# SLAYER_ESP32_M1U.net
KiCad netlist of a schematic drawn in Altium Designer
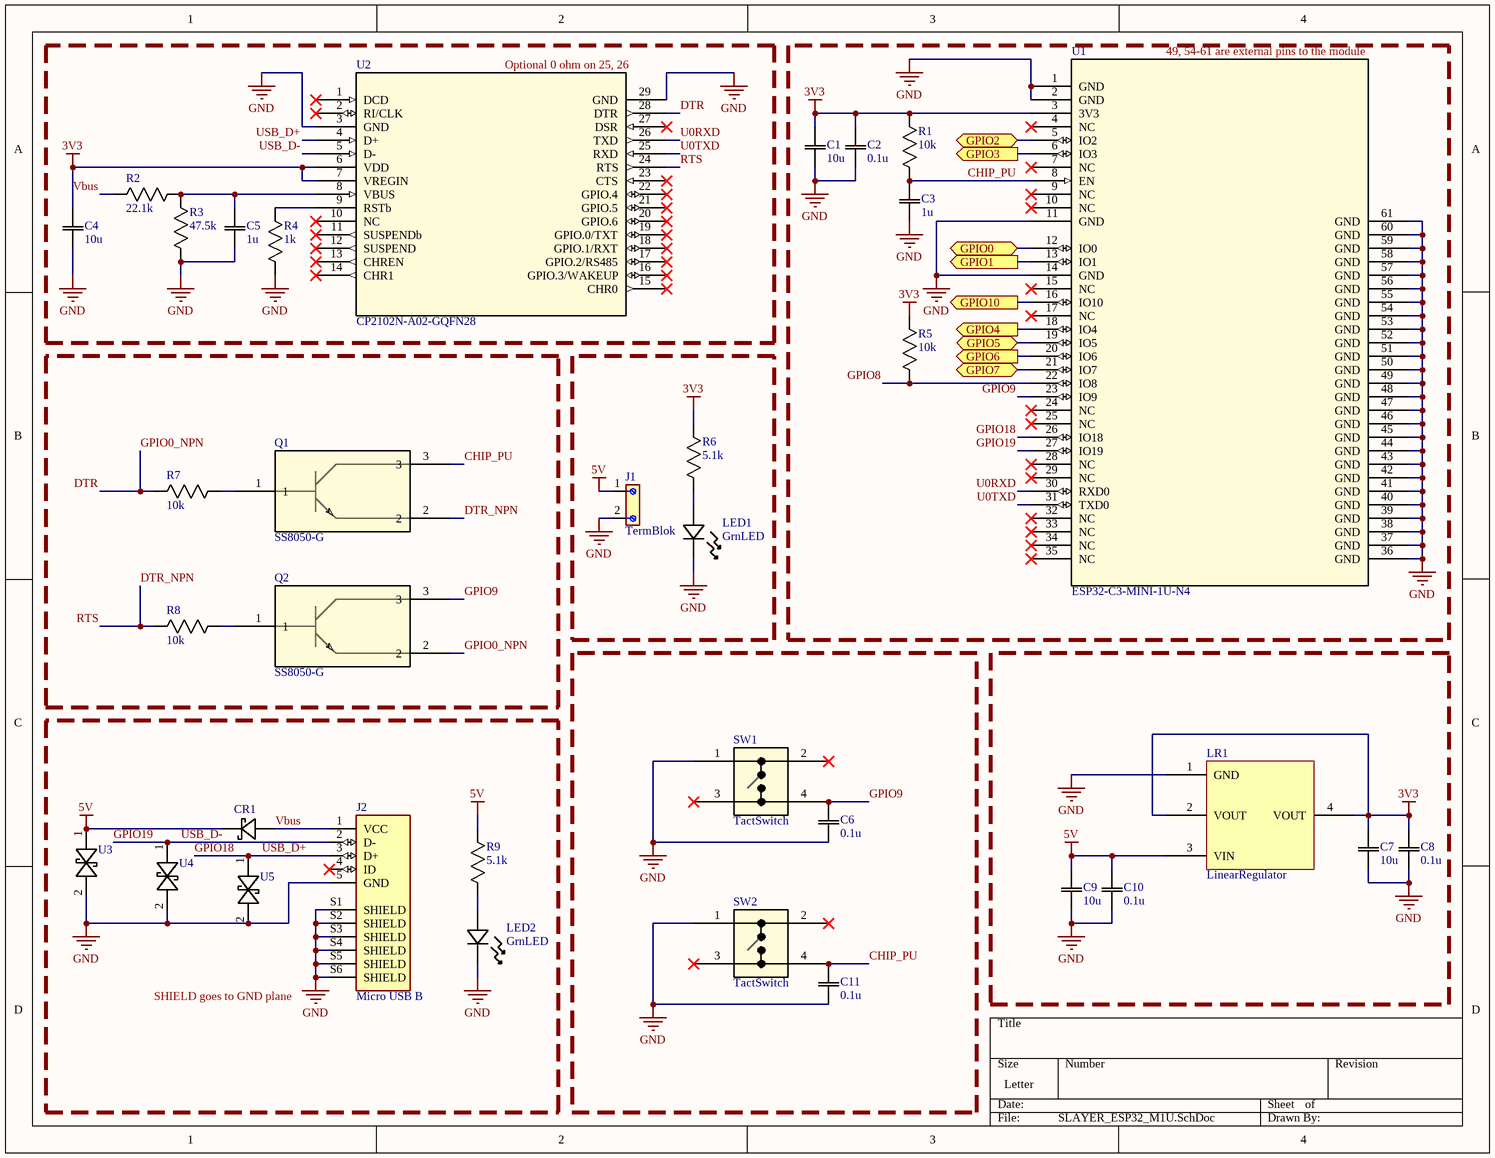
[diagram p0: SLAYER_ESP32_M1U.SchDoc]

(export (version "E")
  (design (tool "Eeschema 10.0.6"))
  (components
    (comp (ref "C1")
      (value "10u")
      (footprint "10uF/25V/0603")
      (description "GRM188R61E106KA73D")
      (fields (field (name "COPYRIGHT") "Copyright (C) 2026 Ultra Librarian. All rights reserved."))
      (libsource (lib "SLAYER_Altium_Sch") (part "10uF/25V"))
    )
    (comp (ref "C2")
      (value "0.1u")
      (footprint "0.1uF/50V")
      (description "CC0603KRX7R9BB104")
      (fields (field (name "COPYRIGHT") "Copyright (C) 2025 Ultra Librarian. All rights reserved."))
      (libsource (lib "SLAYER_Altium_Sch") (part "0.1uF/50V"))
    )
    (comp (ref "C3")
      (value "1u")
      (footprint "1uF/16V")
      (description "CL10B105KO8NNNC")
      (fields (field (name "COPYRIGHT") "Copyright (C) 2025 Ultra Librarian. All rights reserved."))
      (libsource (lib "SLAYER_Altium_Sch") (part "1uF/16V"))
    )
    (comp (ref "C4")
      (value "10u")
      (footprint "10uF/25V/0603")
      (description "GRM188R61E106KA73D")
      (fields (field (name "COPYRIGHT") "Copyright (C) 2026 Ultra Librarian. All rights reserved."))
      (libsource (lib "SLAYER_Altium_Sch") (part "10uF/25V"))
    )
    (comp (ref "C5")
      (value "1u")
      (footprint "1uF/16V")
      (description "CL10B105KO8NNNC")
      (fields (field (name "COPYRIGHT") "Copyright (C) 2025 Ultra Librarian. All rights reserved."))
      (libsource (lib "SLAYER_Altium_Sch") (part "1uF/16V"))
    )
    (comp (ref "C6")
      (value "0.1u")
      (footprint "0.1uF/50V")
      (description "CC0603KRX7R9BB104")
      (fields (field (name "COPYRIGHT") "Copyright (C) 2025 Ultra Librarian. All rights reserved."))
      (libsource (lib "SLAYER_Altium_Sch") (part "0.1uF/50V"))
    )
    (comp (ref "C7")
      (value "10u")
      (footprint "10uF/25V/0603")
      (description "GRM188R61E106KA73D")
      (fields (field (name "COPYRIGHT") "Copyright (C) 2026 Ultra Librarian. All rights reserved."))
      (libsource (lib "SLAYER_Altium_Sch") (part "10uF/25V"))
    )
    (comp (ref "C8")
      (value "0.1u")
      (footprint "0.1uF/50V")
      (description "CC0603KRX7R9BB104")
      (fields (field (name "COPYRIGHT") "Copyright (C) 2025 Ultra Librarian. All rights reserved."))
      (libsource (lib "SLAYER_Altium_Sch") (part "0.1uF/50V"))
    )
    (comp (ref "C9")
      (value "10u")
      (footprint "10uF/25V/0603")
      (description "GRM188R61E106KA73D")
      (fields (field (name "COPYRIGHT") "Copyright (C) 2026 Ultra Librarian. All rights reserved."))
      (libsource (lib "SLAYER_Altium_Sch") (part "10uF/25V"))
    )
    (comp (ref "C10")
      (value "0.1u")
      (footprint "0.1uF/50V")
      (description "CC0603KRX7R9BB104")
      (fields (field (name "COPYRIGHT") "Copyright (C) 2025 Ultra Librarian. All rights reserved."))
      (libsource (lib "SLAYER_Altium_Sch") (part "0.1uF/50V"))
    )
    (comp (ref "C11")
      (value "0.1u")
      (footprint "0.1uF/50V")
      (description "CC0603KRX7R9BB104")
      (fields (field (name "COPYRIGHT") "Copyright (C) 2025 Ultra Librarian. All rights reserved."))
      (libsource (lib "SLAYER_Altium_Sch") (part "0.1uF/50V"))
    )
    (comp (ref "CR1")
      (value "B5819W-TP")
      (footprint "Schottky Diode")
      (fields (field (name "COPYRIGHT") "Copyright (C) 2025 Ultra Librarian. All rights reserved."))
      (libsource (lib "SLAYER_Altium_Sch") (part "Schottky Diode"))
    )
    (comp (ref "J1")
      (value "TermBlok")
      (footprint "TerminalBlock")
      (description "691137710002")
      (fields (field (name "MF") "WÃ¼rth Elektronik"))
      (libsource (lib "SLAYER_Altium_Sch") (part "2TerminalBlock"))
    )
    (comp (ref "J2")
      (value "Micro USB B")
      (footprint "Micro_USB_B")
      (description "10118192-0002LF")
      (fields (field (name "MF") "Amphenol ICC"))
      (libsource (lib "SLAYER_Altium_Sch") (part "Micro USB B"))
    )
    (comp (ref "LED1")
      (value "GrnLED")
      (footprint "GreenLED")
      (description "LTST-C190KGKT")
      (fields (field (name "COPYRIGHT") "Copyright (C) 2025 Ultra Librarian. All rights reserved."))
      (libsource (lib "SLAYER_Altium_Sch") (part "GreenLED"))
    )
    (comp (ref "LED2")
      (value "GrnLED")
      (footprint "GreenLED")
      (description "LTST-C190KGKT")
      (fields (field (name "COPYRIGHT") "Copyright (C) 2025 Ultra Librarian. All rights reserved."))
      (libsource (lib "SLAYER_Altium_Sch") (part "GreenLED"))
    )
    (comp (ref "LR1")
      (value "LinearRegulator")
      (footprint "LinearRegulator")
      (description "SGM2212-3.3XKC3G/TR")
      (libsource (lib "SLAYER_Altium_Sch") (part "LinearRegulator"))
    )
    (comp (ref "Q1")
      (value "SS8050-G")
      (footprint "NPN/25V/1.5A")
      (fields (field (name "COPYRIGHT") "Copyright (C) 2026 Ultra Librarian. All rights reserved."))
      (libsource (lib "SLAYER_Altium_Sch") (part "NPN/25V/1.5A"))
    )
    (comp (ref "Q2")
      (value "SS8050-G")
      (footprint "NPN/25V/1.5A")
      (fields (field (name "COPYRIGHT") "Copyright (C) 2026 Ultra Librarian. All rights reserved."))
      (libsource (lib "SLAYER_Altium_Sch") (part "NPN/25V/1.5A"))
    )
    (comp (ref "R1")
      (value "10k")
      (footprint "10k/0.125W")
      (description "CRCW060310K0FKEA")
      (fields (field (name "COPYRIGHT") "Copyright (C) 2025 Ultra Librarian. All rights reserved."))
      (libsource (lib "SLAYER_Altium_Sch") (part "10k/0.125W"))
    )
    (comp (ref "R2")
      (value "22.1k")
      (footprint "22.1k/0.125W")
      (description "CRCW060322K1FKEA")
      (fields (field (name "COPYRIGHT") "Copyright (C) 2025 Ultra Librarian. All rights reserved."))
      (libsource (lib "SLAYER_Altium_Sch") (part "22.1k/0.125W"))
    )
    (comp (ref "R3")
      (value "47.5k")
      (footprint "47.5k/0.125W")
      (description "CRCW060347K5FKEA")
      (fields (field (name "COPYRIGHT") "Copyright (C) 2026 Ultra Librarian. All rights reserved."))
      (libsource (lib "SLAYER_Altium_Sch") (part "47.5k/0.125W"))
    )
    (comp (ref "R4")
      (value "1k")
      (footprint "1k/0.125W")
      (description "CRCW06031K00FKEA")
      (fields (field (name "COPYRIGHT") "Copyright (C) 2026 Ultra Librarian. All rights reserved."))
      (libsource (lib "SLAYER_Altium_Sch") (part "1k/0.125W"))
    )
    (comp (ref "R5")
      (value "10k")
      (footprint "10k/0.125W")
      (description "CRCW060310K0FKEA")
      (fields (field (name "COPYRIGHT") "Copyright (C) 2025 Ultra Librarian. All rights reserved."))
      (libsource (lib "SLAYER_Altium_Sch") (part "10k/0.125W"))
    )
    (comp (ref "R6")
      (value "5.1k")
      (footprint "5.1k/0.25W")
      (description "CRCW08055K10FKEA")
      (fields (field (name "COPYRIGHT") "Copyright (C) 2026 Ultra Librarian. All rights reserved."))
      (libsource (lib "SLAYER_Altium_Sch") (part "5.1k/0.25W"))
    )
    (comp (ref "R7")
      (value "10k")
      (footprint "10k/0.125W")
      (description "CRCW060310K0FKEA")
      (fields (field (name "COPYRIGHT") "Copyright (C) 2025 Ultra Librarian. All rights reserved."))
      (libsource (lib "SLAYER_Altium_Sch") (part "10k/0.125W"))
    )
    (comp (ref "R8")
      (value "10k")
      (footprint "10k/0.125W")
      (description "CRCW060310K0FKEA")
      (fields (field (name "COPYRIGHT") "Copyright (C) 2025 Ultra Librarian. All rights reserved."))
      (libsource (lib "SLAYER_Altium_Sch") (part "10k/0.125W"))
    )
    (comp (ref "R9")
      (value "5.1k")
      (footprint "5.1k/0.25W")
      (description "CRCW08055K10FKEA")
      (fields (field (name "COPYRIGHT") "Copyright (C) 2026 Ultra Librarian. All rights reserved."))
      (libsource (lib "SLAYER_Altium_Sch") (part "5.1k/0.25W"))
    )
    (comp (ref "SW1")
      (value "TactSwitch")
      (footprint "TactSwitch")
      (description "PTS815 SJM 250 SMTR LFS")
      (fields (field (name "COPYRIGHT") "Copyright (C) 2026 Ultra Librarian. All rights reserved."))
      (libsource (lib "SLAYER_Altium_Sch") (part "TactSwitch"))
    )
    (comp (ref "SW2")
      (value "TactSwitch")
      (footprint "TactSwitch")
      (description "PTS815 SJM 250 SMTR LFS")
      (fields (field (name "COPYRIGHT") "Copyright (C) 2026 Ultra Librarian. All rights reserved."))
      (libsource (lib "SLAYER_Altium_Sch") (part "TactSwitch"))
    )
    (comp (ref "U1")
      (value "ESP32-C3-MINI-1U-N4")
      (footprint "ESP32-C3-MINI-1U_EXP")
      (description "Description")
      (fields (field (name "COPYRIGHT") "Copyright (C) 2025 Ultra Librarian. All rights reserved."))
      (libsource (lib "SLAYER_Altium_Sch") (part "ESP32-C3-MINI-1U-N4"))
    )
    (comp (ref "U2")
      (value "CP2102N-A02-GQFN28")
      (footprint "USB to UART")
      (fields (field (name "COPYRIGHT") "Copyright (C) 2025 Ultra Librarian. All rights reserved."))
      (libsource (lib "SLAYER_Altium_Sch") (part "USB to UART"))
    )
    (comp (ref "U3")
      (value "ESD5B5.0ST1G")
      (footprint "TVS Diode")
      (fields (field (name "COPYRIGHT") "Copyright (C) 2025 Ultra Librarian. All rights reserved."))
      (libsource (lib "SLAYER_Altium_Sch") (part "TVS Diode"))
    )
    (comp (ref "U4")
      (value "ESD5B5.0ST1G")
      (footprint "TVS Diode")
      (fields (field (name "COPYRIGHT") "Copyright (C) 2025 Ultra Librarian. All rights reserved."))
      (libsource (lib "SLAYER_Altium_Sch") (part "TVS Diode"))
    )
    (comp (ref "U5")
      (value "ESD5B5.0ST1G")
      (footprint "TVS Diode")
      (fields (field (name "COPYRIGHT") "Copyright (C) 2025 Ultra Librarian. All rights reserved."))
      (libsource (lib "SLAYER_Altium_Sch") (part "TVS Diode"))
    )
  )
  (nets
    (net (code "1") (name "/CHIP_PU") (class "Default")
      (node (ref "C11") (pin "2") (pinfunction "2_2") (pintype "passive"))
      (node (ref "C3") (pin "2") (pinfunction "2_2") (pintype "passive"))
      (node (ref "Q1") (pin "3") (pinfunction "3_3") (pintype "passive"))
      (node (ref "R1") (pin "2") (pinfunction "2_2") (pintype "passive"))
      (node (ref "SW2") (pin "4") (pinfunction "4_4") (pintype "passive"))
      (node (ref "U1") (pin "8") (pinfunction "EN_8") (pintype "input"))
    )
    (net (code "2") (name "/DTR") (class "Default")
      (node (ref "Q2") (pin "2") (pinfunction "2_2") (pintype "passive"))
      (node (ref "R7") (pin "2") (pinfunction "2_2") (pintype "passive"))
      (node (ref "U2") (pin "28") (pinfunction "DTR_28") (pintype "output"))
    )
    (net (code "3") (name "/DTR_NPN") (class "Default")
      (node (ref "Q1") (pin "2") (pinfunction "2_2") (pintype "passive"))
      (node (ref "R8") (pin "2") (pinfunction "2_2") (pintype "passive"))
      (node (ref "U2") (pin "24") (pinfunction "RTS_24") (pintype "output"))
    )
    (net (code "4") (name "/GPIO0") (class "Default")
      (node (ref "U1") (pin "12") (pinfunction "IO0_12") (pintype "bidirectional"))
    )
    (net (code "5") (name "/GPIO1") (class "Default")
      (node (ref "U1") (pin "13") (pinfunction "IO1_13") (pintype "bidirectional"))
    )
    (net (code "6") (name "/GPIO2") (class "Default")
      (node (ref "U1") (pin "5") (pinfunction "IO2_5") (pintype "bidirectional"))
    )
    (net (code "7") (name "/GPIO3") (class "Default")
      (node (ref "U1") (pin "6") (pinfunction "IO3_6") (pintype "bidirectional"))
    )
    (net (code "8") (name "/GPIO4") (class "Default")
      (node (ref "U1") (pin "18") (pinfunction "IO4_18") (pintype "bidirectional"))
    )
    (net (code "9") (name "/GPIO5") (class "Default")
      (node (ref "U1") (pin "19") (pinfunction "IO5_19") (pintype "bidirectional"))
    )
    (net (code "10") (name "/GPIO6") (class "Default")
      (node (ref "U1") (pin "20") (pinfunction "IO6_20") (pintype "bidirectional"))
    )
    (net (code "11") (name "/GPIO7") (class "Default")
      (node (ref "U1") (pin "21") (pinfunction "IO7_21") (pintype "bidirectional"))
    )
    (net (code "12") (name "/GPIO8") (class "Default")
      (node (ref "R5") (pin "2") (pinfunction "2_2") (pintype "passive"))
      (node (ref "U1") (pin "22") (pinfunction "IO8_22") (pintype "bidirectional"))
    )
    (net (code "13") (name "/GPIO9") (class "Default")
      (node (ref "C6") (pin "2") (pinfunction "2_2") (pintype "passive"))
      (node (ref "Q2") (pin "3") (pinfunction "3_3") (pintype "passive"))
      (node (ref "SW1") (pin "4") (pinfunction "4_4") (pintype "passive"))
      (node (ref "U1") (pin "23") (pinfunction "IO9_23") (pintype "bidirectional"))
    )
    (net (code "14") (name "/GPIO10") (class "Default")
      (node (ref "U1") (pin "16") (pinfunction "IO10_16") (pintype "bidirectional"))
    )
    (net (code "15") (name "/GPIO18") (class "Default")
      (node (ref "J2") (pin "3") (pinfunction "D+_3") (pintype "bidirectional"))
      (node (ref "U1") (pin "26") (pinfunction "IO18_26") (pintype "bidirectional"))
      (node (ref "U2") (pin "4") (pinfunction "D+_4") (pintype "input"))
      (node (ref "U5") (pin "1") (pinfunction "1_1") (pintype "passive"))
    )
    (net (code "16") (name "/GPIO19") (class "Default")
      (node (ref "J2") (pin "2") (pinfunction "D-_2") (pintype "bidirectional"))
      (node (ref "U1") (pin "27") (pinfunction "IO19_27") (pintype "bidirectional"))
      (node (ref "U2") (pin "5") (pinfunction "D-_5") (pintype "input"))
      (node (ref "U4") (pin "1") (pinfunction "1_1") (pintype "passive"))
    )
    (net (code "17") (name "/U0RXD") (class "Default")
      (node (ref "U1") (pin "30") (pinfunction "RXD0_30") (pintype "bidirectional"))
      (node (ref "U2") (pin "26") (pinfunction "TXD_26") (pintype "output"))
    )
    (net (code "18") (name "/U0TXD") (class "Default")
      (node (ref "U1") (pin "31") (pinfunction "TXD0_31") (pintype "bidirectional"))
      (node (ref "U2") (pin "25") (pinfunction "RXD_25") (pintype "input"))
    )
    (net (code "19") (name "/Vbus") (class "Default")
      (node (ref "CR1") (pin "2") (pinfunction "2_2") (pintype "passive"))
      (node (ref "J2") (pin "1") (pinfunction "VCC_1") (pintype "power_in"))
      (node (ref "R2") (pin "2") (pinfunction "2_2") (pintype "passive"))
    )
    (net (code "20") (name "3V3") (class "Default")
      (node (ref "C1") (pin "2") (pinfunction "2_2") (pintype "passive"))
      (node (ref "C2") (pin "2") (pinfunction "2_2") (pintype "passive"))
      (node (ref "C4") (pin "2") (pinfunction "2_2") (pintype "passive"))
      (node (ref "C7") (pin "2") (pinfunction "2_2") (pintype "passive"))
      (node (ref "C8") (pin "2") (pinfunction "2_2") (pintype "passive"))
      (node (ref "LR1") (pin "2") (pinfunction "VOUT_2") (pintype "power_in"))
      (node (ref "LR1") (pin "4") (pinfunction "VOUT_4") (pintype "power_in"))
      (node (ref "R1") (pin "1") (pinfunction "1_1") (pintype "passive"))
      (node (ref "R5") (pin "1") (pinfunction "1_1") (pintype "passive"))
      (node (ref "R6") (pin "1") (pinfunction "1_1") (pintype "passive"))
      (node (ref "U1") (pin "3") (pinfunction "3V3_3") (pintype "power_in"))
      (node (ref "U2") (pin "6") (pinfunction "VDD_6") (pintype "power_in"))
      (node (ref "U2") (pin "7") (pinfunction "VREGIN_7") (pintype "power_in"))
    )
    (net (code "21") (name "5V") (class "Default")
      (node (ref "C10") (pin "2") (pinfunction "2_2") (pintype "passive"))
      (node (ref "C9") (pin "2") (pinfunction "2_2") (pintype "passive"))
      (node (ref "CR1") (pin "1") (pinfunction "1_1") (pintype "passive"))
      (node (ref "J1") (pin "1") (pinfunction "1_1") (pintype "passive"))
      (node (ref "LR1") (pin "3") (pinfunction "VIN_3") (pintype "power_in"))
      (node (ref "R9") (pin "1") (pinfunction "1_1") (pintype "passive"))
      (node (ref "U3") (pin "1") (pinfunction "1_1") (pintype "passive"))
    )
    (net (code "22") (name "GND") (class "Default")
      (node (ref "C1") (pin "1") (pinfunction "1_1") (pintype "passive"))
      (node (ref "C10") (pin "1") (pinfunction "1_1") (pintype "passive"))
      (node (ref "C11") (pin "1") (pinfunction "1_1") (pintype "passive"))
      (node (ref "C2") (pin "1") (pinfunction "1_1") (pintype "passive"))
      (node (ref "C3") (pin "1") (pinfunction "1_1") (pintype "passive"))
      (node (ref "C4") (pin "1") (pinfunction "1_1") (pintype "passive"))
      (node (ref "C5") (pin "1") (pinfunction "1_1") (pintype "passive"))
      (node (ref "C6") (pin "1") (pinfunction "1_1") (pintype "passive"))
      (node (ref "C7") (pin "1") (pinfunction "1_1") (pintype "passive"))
      (node (ref "C8") (pin "1") (pinfunction "1_1") (pintype "passive"))
      (node (ref "C9") (pin "1") (pinfunction "1_1") (pintype "passive"))
      (node (ref "J1") (pin "2") (pinfunction "2_2") (pintype "passive"))
      (node (ref "J2") (pin "5") (pinfunction "GND_5") (pintype "power_in"))
      (node (ref "J2") (pin "S1") (pinfunction "SHIELD_S1") (pintype "passive"))
      (node (ref "J2") (pin "S2") (pinfunction "SHIELD_S2") (pintype "passive"))
      (node (ref "J2") (pin "S3") (pinfunction "SHIELD_S3") (pintype "passive"))
      (node (ref "J2") (pin "S4") (pinfunction "SHIELD_S4") (pintype "passive"))
      (node (ref "J2") (pin "S5") (pinfunction "SHIELD_S5") (pintype "passive"))
      (node (ref "J2") (pin "S6") (pinfunction "SHIELD_S6") (pintype "passive"))
      (node (ref "LED1") (pin "1") (pinfunction "1_1") (pintype "passive"))
      (node (ref "LED2") (pin "1") (pinfunction "1_1") (pintype "passive"))
      (node (ref "LR1") (pin "1") (pinfunction "GND_1") (pintype "power_in"))
      (node (ref "R3") (pin "2") (pinfunction "2_2") (pintype "passive"))
      (node (ref "R4") (pin "2") (pinfunction "2_2") (pintype "passive"))
      (node (ref "SW1") (pin "1") (pinfunction "1_1") (pintype "passive"))
      (node (ref "SW2") (pin "1") (pinfunction "1_1") (pintype "passive"))
      (node (ref "U1") (pin "1") (pinfunction "GND_1") (pintype "power_in"))
      (node (ref "U1") (pin "11") (pinfunction "GND_11") (pintype "power_in"))
      (node (ref "U1") (pin "14") (pinfunction "GND_14") (pintype "power_in"))
      (node (ref "U1") (pin "2") (pinfunction "GND_2") (pintype "power_in"))
      (node (ref "U1") (pin "36") (pinfunction "GND_36") (pintype "power_in"))
      (node (ref "U1") (pin "37") (pinfunction "GND_37") (pintype "power_in"))
      (node (ref "U1") (pin "38") (pinfunction "GND_38") (pintype "power_in"))
      (node (ref "U1") (pin "39") (pinfunction "GND_39") (pintype "power_in"))
      (node (ref "U1") (pin "40") (pinfunction "GND_40") (pintype "power_in"))
      (node (ref "U1") (pin "41") (pinfunction "GND_41") (pintype "power_in"))
      (node (ref "U1") (pin "42") (pinfunction "GND_42") (pintype "power_in"))
      (node (ref "U1") (pin "43") (pinfunction "GND_43") (pintype "power_in"))
      (node (ref "U1") (pin "44") (pinfunction "GND_44") (pintype "power_in"))
      (node (ref "U1") (pin "45") (pinfunction "GND_45") (pintype "power_in"))
      (node (ref "U1") (pin "46") (pinfunction "GND_46") (pintype "power_in"))
      (node (ref "U1") (pin "47") (pinfunction "GND_47") (pintype "power_in"))
      (node (ref "U1") (pin "48") (pinfunction "GND_48") (pintype "power_in"))
      (node (ref "U1") (pin "49") (pinfunction "GND_49") (pintype "power_in"))
      (node (ref "U1") (pin "50") (pinfunction "GND_50") (pintype "power_in"))
      (node (ref "U1") (pin "51") (pinfunction "GND_51") (pintype "power_in"))
      (node (ref "U1") (pin "52") (pinfunction "GND_52") (pintype "power_in"))
      (node (ref "U1") (pin "53") (pinfunction "GND_53") (pintype "power_in"))
      (node (ref "U1") (pin "54") (pinfunction "GND_54") (pintype "power_in"))
      (node (ref "U1") (pin "55") (pinfunction "GND_55") (pintype "power_in"))
      (node (ref "U1") (pin "56") (pinfunction "GND_56") (pintype "power_in"))
      (node (ref "U1") (pin "57") (pinfunction "GND_57") (pintype "power_in"))
      (node (ref "U1") (pin "58") (pinfunction "GND_58") (pintype "power_in"))
      (node (ref "U1") (pin "59") (pinfunction "GND_59") (pintype "power_in"))
      (node (ref "U1") (pin "60") (pinfunction "GND_60") (pintype "power_in"))
      (node (ref "U1") (pin "61") (pinfunction "GND_61") (pintype "power_in"))
      (node (ref "U2") (pin "29") (pinfunction "GND_29") (pintype "power_in"))
      (node (ref "U2") (pin "3") (pinfunction "GND_3") (pintype "power_in"))
      (node (ref "U3") (pin "2") (pinfunction "2_2") (pintype "passive"))
      (node (ref "U4") (pin "2") (pinfunction "2_2") (pintype "passive"))
      (node (ref "U5") (pin "2") (pinfunction "2_2") (pintype "passive"))
    )
    (net (code "23") (name "Net-(LED1-Pad2)") (class "Default")
      (node (ref "LED1") (pin "2") (pinfunction "2_2") (pintype "passive"))
      (node (ref "R6") (pin "2") (pinfunction "2_2") (pintype "passive"))
    )
    (net (code "24") (name "Net-(LED2-Pad2)") (class "Default")
      (node (ref "LED2") (pin "2") (pinfunction "2_2") (pintype "passive"))
      (node (ref "R9") (pin "2") (pinfunction "2_2") (pintype "passive"))
    )
    (net (code "25") (name "Net-(Q1-Pad1)") (class "Default")
      (node (ref "Q1") (pin "1") (pinfunction "1_1") (pintype "passive"))
      (node (ref "R7") (pin "1") (pinfunction "1_1") (pintype "passive"))
    )
    (net (code "26") (name "Net-(Q2-Pad1)") (class "Default")
      (node (ref "Q2") (pin "1") (pinfunction "1_1") (pintype "passive"))
      (node (ref "R8") (pin "1") (pinfunction "1_1") (pintype "passive"))
    )
    (net (code "27") (name "Net-(U2-RSTb)") (class "Default")
      (node (ref "R4") (pin "1") (pinfunction "1_1") (pintype "passive"))
      (node (ref "U2") (pin "9") (pinfunction "RSTb_9") (pintype "passive"))
    )
    (net (code "28") (name "Net-(U2-VBUS)") (class "Default")
      (node (ref "C5") (pin "2") (pinfunction "2_2") (pintype "passive"))
      (node (ref "R2") (pin "1") (pinfunction "1_1") (pintype "passive"))
      (node (ref "R3") (pin "1") (pinfunction "1_1") (pintype "passive"))
      (node (ref "U2") (pin "8") (pinfunction "VBUS_8") (pintype "input"))
    )
    (net (code "29") (name "unconnected-(J2-ID-Pad4)") (class "Default")
      (node (ref "J2") (pin "4") (pinfunction "ID_4") (pintype "bidirectional+no_connect"))
    )
    (net (code "30") (name "unconnected-(SW1-Pad2)") (class "Default")
      (node (ref "SW1") (pin "2") (pinfunction "2_2") (pintype "passive+no_connect"))
    )
    (net (code "31") (name "unconnected-(SW1-Pad3)") (class "Default")
      (node (ref "SW1") (pin "3") (pinfunction "3_3") (pintype "passive+no_connect"))
    )
    (net (code "32") (name "unconnected-(SW2-Pad2)") (class "Default")
      (node (ref "SW2") (pin "2") (pinfunction "2_2") (pintype "passive+no_connect"))
    )
    (net (code "33") (name "unconnected-(SW2-Pad3)") (class "Default")
      (node (ref "SW2") (pin "3") (pinfunction "3_3") (pintype "passive+no_connect"))
    )
    (net (code "34") (name "unconnected-(U1-NC-Pad4)") (class "Default")
      (node (ref "U1") (pin "4") (pinfunction "NC_4") (pintype "passive+no_connect"))
    )
    (net (code "35") (name "unconnected-(U1-NC-Pad7)") (class "Default")
      (node (ref "U1") (pin "7") (pinfunction "NC_7") (pintype "passive+no_connect"))
    )
    (net (code "36") (name "unconnected-(U1-NC-Pad9)") (class "Default")
      (node (ref "U1") (pin "9") (pinfunction "NC_9") (pintype "passive+no_connect"))
    )
    (net (code "37") (name "unconnected-(U1-NC-Pad10)") (class "Default")
      (node (ref "U1") (pin "10") (pinfunction "NC_10") (pintype "passive+no_connect"))
    )
    (net (code "38") (name "unconnected-(U1-NC-Pad15)") (class "Default")
      (node (ref "U1") (pin "15") (pinfunction "NC_15") (pintype "passive+no_connect"))
    )
    (net (code "39") (name "unconnected-(U1-NC-Pad17)") (class "Default")
      (node (ref "U1") (pin "17") (pinfunction "NC_17") (pintype "passive+no_connect"))
    )
    (net (code "40") (name "unconnected-(U1-NC-Pad24)") (class "Default")
      (node (ref "U1") (pin "24") (pinfunction "NC_24") (pintype "passive+no_connect"))
    )
    (net (code "41") (name "unconnected-(U1-NC-Pad25)") (class "Default")
      (node (ref "U1") (pin "25") (pinfunction "NC_25") (pintype "passive+no_connect"))
    )
    (net (code "42") (name "unconnected-(U1-NC-Pad28)") (class "Default")
      (node (ref "U1") (pin "28") (pinfunction "NC_28") (pintype "passive+no_connect"))
    )
    (net (code "43") (name "unconnected-(U1-NC-Pad29)") (class "Default")
      (node (ref "U1") (pin "29") (pinfunction "NC_29") (pintype "passive+no_connect"))
    )
    (net (code "44") (name "unconnected-(U1-NC-Pad32)") (class "Default")
      (node (ref "U1") (pin "32") (pinfunction "NC_32") (pintype "passive+no_connect"))
    )
    (net (code "45") (name "unconnected-(U1-NC-Pad33)") (class "Default")
      (node (ref "U1") (pin "33") (pinfunction "NC_33") (pintype "passive+no_connect"))
    )
    (net (code "46") (name "unconnected-(U1-NC-Pad34)") (class "Default")
      (node (ref "U1") (pin "34") (pinfunction "NC_34") (pintype "passive+no_connect"))
    )
    (net (code "47") (name "unconnected-(U1-NC-Pad35)") (class "Default")
      (node (ref "U1") (pin "35") (pinfunction "NC_35") (pintype "passive+no_connect"))
    )
    (net (code "48") (name "unconnected-(U2-CHR0-Pad15)") (class "Default")
      (node (ref "U2") (pin "15") (pinfunction "CHR0_15") (pintype "output+no_connect"))
    )
    (net (code "49") (name "unconnected-(U2-CHR1-Pad14)") (class "Default")
      (node (ref "U2") (pin "14") (pinfunction "CHR1_14") (pintype "output+no_connect"))
    )
    (net (code "50") (name "unconnected-(U2-CHREN-Pad13)") (class "Default")
      (node (ref "U2") (pin "13") (pinfunction "CHREN_13") (pintype "output+no_connect"))
    )
    (net (code "51") (name "unconnected-(U2-CTS-Pad23)") (class "Default")
      (node (ref "U2") (pin "23") (pinfunction "CTS_23") (pintype "input+no_connect"))
    )
    (net (code "52") (name "unconnected-(U2-DCD-Pad1)") (class "Default")
      (node (ref "U2") (pin "1") (pinfunction "DCD_1") (pintype "input+no_connect"))
    )
    (net (code "53") (name "unconnected-(U2-DSR-Pad27)") (class "Default")
      (node (ref "U2") (pin "27") (pinfunction "DSR_27") (pintype "input+no_connect"))
    )
    (net (code "54") (name "unconnected-(U2-GPIO.0{slash}TXT-Pad19)") (class "Default")
      (node (ref "U2") (pin "19") (pinfunction "GPIO.0/TXT_19") (pintype "bidirectional+no_connect"))
    )
    (net (code "55") (name "unconnected-(U2-GPIO.1{slash}RXT-Pad18)") (class "Default")
      (node (ref "U2") (pin "18") (pinfunction "GPIO.1/RXT_18") (pintype "bidirectional+no_connect"))
    )
    (net (code "56") (name "unconnected-(U2-GPIO.2{slash}RS485-Pad17)") (class "Default")
      (node (ref "U2") (pin "17") (pinfunction "GPIO.2/RS485_17") (pintype "bidirectional+no_connect"))
    )
    (net (code "57") (name "unconnected-(U2-GPIO.3{slash}WAKEUP-Pad16)") (class "Default")
      (node (ref "U2") (pin "16") (pinfunction "GPIO.3/WAKEUP_16") (pintype "bidirectional+no_connect"))
    )
    (net (code "58") (name "unconnected-(U2-GPIO.4-Pad22)") (class "Default")
      (node (ref "U2") (pin "22") (pinfunction "GPIO.4_22") (pintype "bidirectional+no_connect"))
    )
    (net (code "59") (name "unconnected-(U2-GPIO.5-Pad21)") (class "Default")
      (node (ref "U2") (pin "21") (pinfunction "GPIO.5_21") (pintype "bidirectional+no_connect"))
    )
    (net (code "60") (name "unconnected-(U2-GPIO.6-Pad20)") (class "Default")
      (node (ref "U2") (pin "20") (pinfunction "GPIO.6_20") (pintype "bidirectional+no_connect"))
    )
    (net (code "61") (name "unconnected-(U2-NC-Pad10)") (class "Default")
      (node (ref "U2") (pin "10") (pinfunction "NC_10") (pintype "passive+no_connect"))
    )
    (net (code "62") (name "unconnected-(U2-RI{slash}CLK-Pad2)") (class "Default")
      (node (ref "U2") (pin "2") (pinfunction "RI/CLK_2") (pintype "bidirectional+no_connect"))
    )
    (net (code "63") (name "unconnected-(U2-SUSPEND-Pad12)") (class "Default")
      (node (ref "U2") (pin "12") (pinfunction "SUSPEND_12") (pintype "output+no_connect"))
    )
    (net (code "64") (name "unconnected-(U2-SUSPENDb-Pad11)") (class "Default")
      (node (ref "U2") (pin "11") (pinfunction "SUSPENDb_11") (pintype "output+no_connect"))
    )
  )
)
